# DualSVF.net
KiCad netlist of a schematic drawn in EAGLE
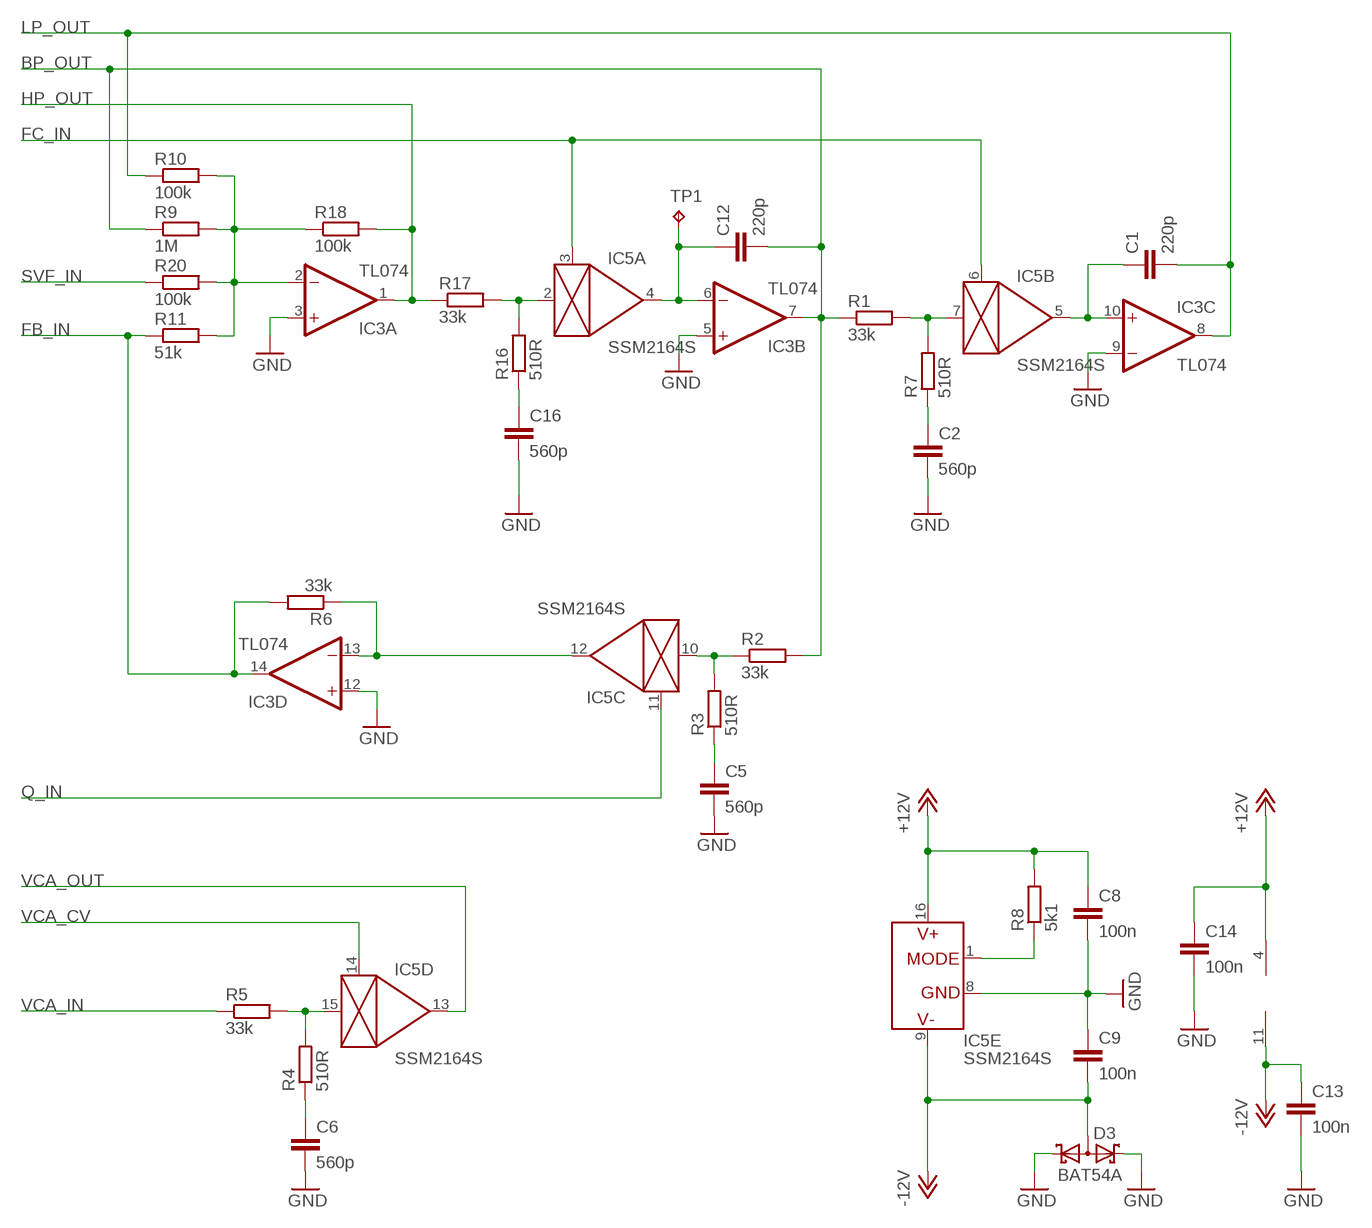
[diagram p0: schematic, sheet 1]

(export (version "E")
  (design (tool "Eeschema 10.0.6"))
  (components
    (comp (ref "C1")
      (value "220p")
      (footprint "eagle-import:C0603")
      (libsource (lib "eagle-import") (part "C-EUC0603"))
    )
    (comp (ref "C2")
      (value "560p")
      (footprint "eagle-import:C0603")
      (libsource (lib "eagle-import") (part "C-EUC0603"))
    )
    (comp (ref "C5")
      (value "560p")
      (footprint "eagle-import:C0603")
      (libsource (lib "eagle-import") (part "C-EUC0603"))
    )
    (comp (ref "C6")
      (value "560p")
      (footprint "eagle-import:C0603")
      (libsource (lib "eagle-import") (part "C-EUC0603"))
    )
    (comp (ref "C8")
      (value "100n")
      (footprint "eagle-import:C0603K")
      (libsource (lib "eagle-import") (part "C-EUC0603K"))
    )
    (comp (ref "C9")
      (value "100n")
      (footprint "eagle-import:C0603K")
      (libsource (lib "eagle-import") (part "C-EUC0603K"))
    )
    (comp (ref "C12")
      (value "220p")
      (footprint "eagle-import:C0603")
      (libsource (lib "eagle-import") (part "C-EUC0603"))
    )
    (comp (ref "C13")
      (value "100n")
      (footprint "eagle-import:C0603K")
      (libsource (lib "eagle-import") (part "C-EUC0603K"))
    )
    (comp (ref "C14")
      (value "100n")
      (footprint "eagle-import:C0603K")
      (libsource (lib "eagle-import") (part "C-EUC0603K"))
    )
    (comp (ref "C16")
      (value "560p")
      (footprint "eagle-import:C0603")
      (libsource (lib "eagle-import") (part "C-EUC0603"))
    )
    (comp (ref "D3")
      (value "BAT54A")
      (footprint "eagle-import:SOT23")
      (libsource (lib "eagle-import") (part "BAT54A"))
    )
    (comp (ref "IC3")
      (value "TL074")
      (footprint "eagle-import:SO14")
      (libsource (lib "eagle-import") (part "TL074D"))
    )
    (comp (ref "IC5")
      (value "SSM2164S")
      (footprint "eagle-import:SOIC16N")
      (libsource (lib "eagle-import") (part "SSM2164S"))
    )
    (comp (ref "R1")
      (value "33k")
      (footprint "eagle-import:0603")
      (libsource (lib "eagle-import") (part "R-EU_0603"))
    )
    (comp (ref "R2")
      (value "33k")
      (footprint "eagle-import:0603")
      (libsource (lib "eagle-import") (part "R-EU_0603"))
    )
    (comp (ref "R3")
      (value "510R")
      (footprint "eagle-import:0603")
      (libsource (lib "eagle-import") (part "R-EU_0603"))
    )
    (comp (ref "R4")
      (value "510R")
      (footprint "eagle-import:0603")
      (libsource (lib "eagle-import") (part "R-EU_0603"))
    )
    (comp (ref "R5")
      (value "33k")
      (footprint "eagle-import:0603")
      (libsource (lib "eagle-import") (part "R-EU_0603"))
    )
    (comp (ref "R6")
      (value "33k")
      (footprint "eagle-import:0603")
      (libsource (lib "eagle-import") (part "R-EU_0603"))
    )
    (comp (ref "R7")
      (value "510R")
      (footprint "eagle-import:0603")
      (libsource (lib "eagle-import") (part "R-EU_0603"))
    )
    (comp (ref "R8")
      (value "5k1")
      (footprint "eagle-import:0603")
      (libsource (lib "eagle-import") (part "R-EU_0603"))
    )
    (comp (ref "R9")
      (value "1M")
      (footprint "eagle-import:0603")
      (libsource (lib "eagle-import") (part "R-EU_0603"))
    )
    (comp (ref "R10")
      (value "100k")
      (footprint "eagle-import:0603")
      (libsource (lib "eagle-import") (part "R-EU_0603"))
    )
    (comp (ref "R11")
      (value "51k")
      (footprint "eagle-import:0603")
      (libsource (lib "eagle-import") (part "R-EU_0603"))
    )
    (comp (ref "R16")
      (value "510R")
      (footprint "eagle-import:0603")
      (libsource (lib "eagle-import") (part "R-EU_0603"))
    )
    (comp (ref "R17")
      (value "33k")
      (footprint "eagle-import:0603")
      (libsource (lib "eagle-import") (part "R-EU_0603"))
    )
    (comp (ref "R18")
      (value "100k")
      (footprint "eagle-import:0603")
      (libsource (lib "eagle-import") (part "R-EU_0603"))
    )
    (comp (ref "R20")
      (value "100k")
      (footprint "eagle-import:0603")
      (libsource (lib "eagle-import") (part "R-EU_0603"))
    )
    (comp (ref "TP1")
      (value "TPPAD1-13")
      (footprint "eagle-import:P1-13")
      (libsource (lib "eagle-import") (part "TPPAD1-13"))
    )
  )
  (nets
    (net (code "1") (name "+12V") (class "Default")
      (node (ref "C14") (pin "1") (pinfunction "1_1") (pintype "passive"))
      (node (ref "C8") (pin "1") (pinfunction "1_1") (pintype "passive"))
      (node (ref "IC3") (pin "4") (pinfunction "V+_4") (pintype "power_in"))
      (node (ref "IC5") (pin "16") (pinfunction "V+_16") (pintype "power_in"))
      (node (ref "R8") (pin "2") (pinfunction "2_2") (pintype "passive"))
    )
    (net (code "2") (name "-12V") (class "Default")
      (node (ref "C13") (pin "1") (pinfunction "1_1") (pintype "passive"))
      (node (ref "C9") (pin "2") (pinfunction "2_2") (pintype "passive"))
      (node (ref "D3") (pin "3") (pinfunction "AA_3") (pintype "passive"))
      (node (ref "IC3") (pin "11") (pinfunction "V-_11") (pintype "power_in"))
      (node (ref "IC5") (pin "9") (pinfunction "V-_9") (pintype "power_in"))
    )
    (net (code "3") (name "/BP_OUT") (class "Default")
      (node (ref "C12") (pin "2") (pinfunction "2_2") (pintype "passive"))
      (node (ref "IC3") (pin "7") (pinfunction "OUT_7") (pintype "output"))
      (node (ref "R1") (pin "1") (pinfunction "1_1") (pintype "passive"))
      (node (ref "R2") (pin "2") (pinfunction "2_2") (pintype "passive"))
      (node (ref "R9") (pin "1") (pinfunction "1_1") (pintype "passive"))
    )
    (net (code "4") (name "/FB_IN") (class "Default")
      (node (ref "IC3") (pin "14") (pinfunction "OUT_14") (pintype "output"))
      (node (ref "R11") (pin "1") (pinfunction "1_1") (pintype "passive"))
      (node (ref "R6") (pin "2") (pinfunction "2_2") (pintype "passive"))
    )
    (net (code "5") (name "/FC_IN") (class "Default")
      (node (ref "IC5") (pin "3") (pinfunction "CTRL_3") (pintype "input"))
      (node (ref "IC5") (pin "6") (pinfunction "CTRL_6") (pintype "input"))
    )
    (net (code "6") (name "/HP_OUT") (class "Default")
      (node (ref "IC3") (pin "1") (pinfunction "OUT_1") (pintype "output"))
      (node (ref "R17") (pin "1") (pinfunction "1_1") (pintype "passive"))
      (node (ref "R18") (pin "2") (pinfunction "2_2") (pintype "passive"))
    )
    (net (code "7") (name "/LP_OUT") (class "Default")
      (node (ref "C1") (pin "2") (pinfunction "2_2") (pintype "passive"))
      (node (ref "IC3") (pin "8") (pinfunction "OUT_8") (pintype "output"))
      (node (ref "R10") (pin "1") (pinfunction "1_1") (pintype "passive"))
    )
    (net (code "8") (name "/Q_IN") (class "Default")
      (node (ref "IC5") (pin "11") (pinfunction "CTRL_11") (pintype "input"))
    )
    (net (code "9") (name "/SVF_IN") (class "Default")
      (node (ref "R20") (pin "1") (pinfunction "1_1") (pintype "passive"))
    )
    (net (code "10") (name "/VCA_CV") (class "Default")
      (node (ref "IC5") (pin "14") (pinfunction "CTRL_14") (pintype "input"))
    )
    (net (code "11") (name "/VCA_IN") (class "Default")
      (node (ref "R5") (pin "1") (pinfunction "1_1") (pintype "passive"))
    )
    (net (code "12") (name "/VCA_OUT") (class "Default")
      (node (ref "IC5") (pin "13") (pinfunction "OUT_13") (pintype "output"))
    )
    (net (code "13") (name "GND") (class "Default")
      (node (ref "C13") (pin "2") (pinfunction "2_2") (pintype "passive"))
      (node (ref "C14") (pin "2") (pinfunction "2_2") (pintype "passive"))
      (node (ref "C16") (pin "2") (pinfunction "2_2") (pintype "passive"))
      (node (ref "C2") (pin "2") (pinfunction "2_2") (pintype "passive"))
      (node (ref "C5") (pin "2") (pinfunction "2_2") (pintype "passive"))
      (node (ref "C6") (pin "2") (pinfunction "2_2") (pintype "passive"))
      (node (ref "C8") (pin "2") (pinfunction "2_2") (pintype "passive"))
      (node (ref "C9") (pin "1") (pinfunction "1_1") (pintype "passive"))
      (node (ref "D3") (pin "1") (pinfunction "K1_1") (pintype "passive"))
      (node (ref "D3") (pin "2") (pinfunction "K2_2") (pintype "passive"))
      (node (ref "IC3") (pin "12") (pinfunction "+IN_12") (pintype "input"))
      (node (ref "IC3") (pin "3") (pinfunction "+IN_3") (pintype "input"))
      (node (ref "IC3") (pin "5") (pinfunction "+IN_5") (pintype "input"))
      (node (ref "IC3") (pin "9") (pinfunction "-IN_9") (pintype "input"))
      (node (ref "IC5") (pin "8") (pinfunction "GND_8") (pintype "power_in"))
    )
    (net (code "14") (name "Net-(C2-Pad1)") (class "Default")
      (node (ref "C2") (pin "1") (pinfunction "1_1") (pintype "passive"))
      (node (ref "R7") (pin "1") (pinfunction "1_1") (pintype "passive"))
    )
    (net (code "15") (name "Net-(C5-Pad1)") (class "Default")
      (node (ref "C5") (pin "1") (pinfunction "1_1") (pintype "passive"))
      (node (ref "R3") (pin "1") (pinfunction "1_1") (pintype "passive"))
    )
    (net (code "16") (name "Net-(C6-Pad1)") (class "Default")
      (node (ref "C6") (pin "1") (pinfunction "1_1") (pintype "passive"))
      (node (ref "R4") (pin "1") (pinfunction "1_1") (pintype "passive"))
    )
    (net (code "17") (name "Net-(C16-Pad1)") (class "Default")
      (node (ref "C16") (pin "1") (pinfunction "1_1") (pintype "passive"))
      (node (ref "R16") (pin "1") (pinfunction "1_1") (pintype "passive"))
    )
    (net (code "18") (name "Net-(IC3A--IN)") (class "Default")
      (node (ref "IC3") (pin "2") (pinfunction "-IN_2") (pintype "input"))
      (node (ref "R10") (pin "2") (pinfunction "2_2") (pintype "passive"))
      (node (ref "R11") (pin "2") (pinfunction "2_2") (pintype "passive"))
      (node (ref "R18") (pin "1") (pinfunction "1_1") (pintype "passive"))
      (node (ref "R20") (pin "2") (pinfunction "2_2") (pintype "passive"))
      (node (ref "R9") (pin "2") (pinfunction "2_2") (pintype "passive"))
    )
    (net (code "19") (name "Net-(IC3B--IN)") (class "Default")
      (node (ref "C12") (pin "1") (pinfunction "1_1") (pintype "passive"))
      (node (ref "IC3") (pin "6") (pinfunction "-IN_6") (pintype "input"))
      (node (ref "IC5") (pin "4") (pinfunction "OUT_4") (pintype "output"))
      (node (ref "TP1") (pin "TP") (pinfunction "TP_TP") (pintype "input"))
    )
    (net (code "20") (name "Net-(IC3C-+IN)") (class "Default")
      (node (ref "C1") (pin "1") (pinfunction "1_1") (pintype "passive"))
      (node (ref "IC3") (pin "10") (pinfunction "+IN_10") (pintype "input"))
      (node (ref "IC5") (pin "5") (pinfunction "OUT_5") (pintype "output"))
    )
    (net (code "21") (name "Net-(IC3D--IN)") (class "Default")
      (node (ref "IC3") (pin "13") (pinfunction "-IN_13") (pintype "input"))
      (node (ref "IC5") (pin "12") (pinfunction "OUT_12") (pintype "output"))
      (node (ref "R6") (pin "1") (pinfunction "1_1") (pintype "passive"))
    )
    (net (code "22") (name "Net-(IC5A-IN)") (class "Default")
      (node (ref "IC5") (pin "2") (pinfunction "IN_2") (pintype "input"))
      (node (ref "R16") (pin "2") (pinfunction "2_2") (pintype "passive"))
      (node (ref "R17") (pin "2") (pinfunction "2_2") (pintype "passive"))
    )
    (net (code "23") (name "Net-(IC5B-IN)") (class "Default")
      (node (ref "IC5") (pin "7") (pinfunction "IN_7") (pintype "input"))
      (node (ref "R1") (pin "2") (pinfunction "2_2") (pintype "passive"))
      (node (ref "R7") (pin "2") (pinfunction "2_2") (pintype "passive"))
    )
    (net (code "24") (name "Net-(IC5C-IN)") (class "Default")
      (node (ref "IC5") (pin "10") (pinfunction "IN_10") (pintype "input"))
      (node (ref "R2") (pin "1") (pinfunction "1_1") (pintype "passive"))
      (node (ref "R3") (pin "2") (pinfunction "2_2") (pintype "passive"))
    )
    (net (code "25") (name "Net-(IC5D-IN)") (class "Default")
      (node (ref "IC5") (pin "15") (pinfunction "IN_15") (pintype "input"))
      (node (ref "R4") (pin "2") (pinfunction "2_2") (pintype "passive"))
      (node (ref "R5") (pin "2") (pinfunction "2_2") (pintype "passive"))
    )
    (net (code "26") (name "Net-(IC5E-MODE)") (class "Default")
      (node (ref "IC5") (pin "1") (pinfunction "MODE_1") (pintype "input"))
      (node (ref "R8") (pin "1") (pinfunction "1_1") (pintype "passive"))
    )
  )
)
